# ESC2.net
KiCad netlist of a schematic drawn in EAGLE
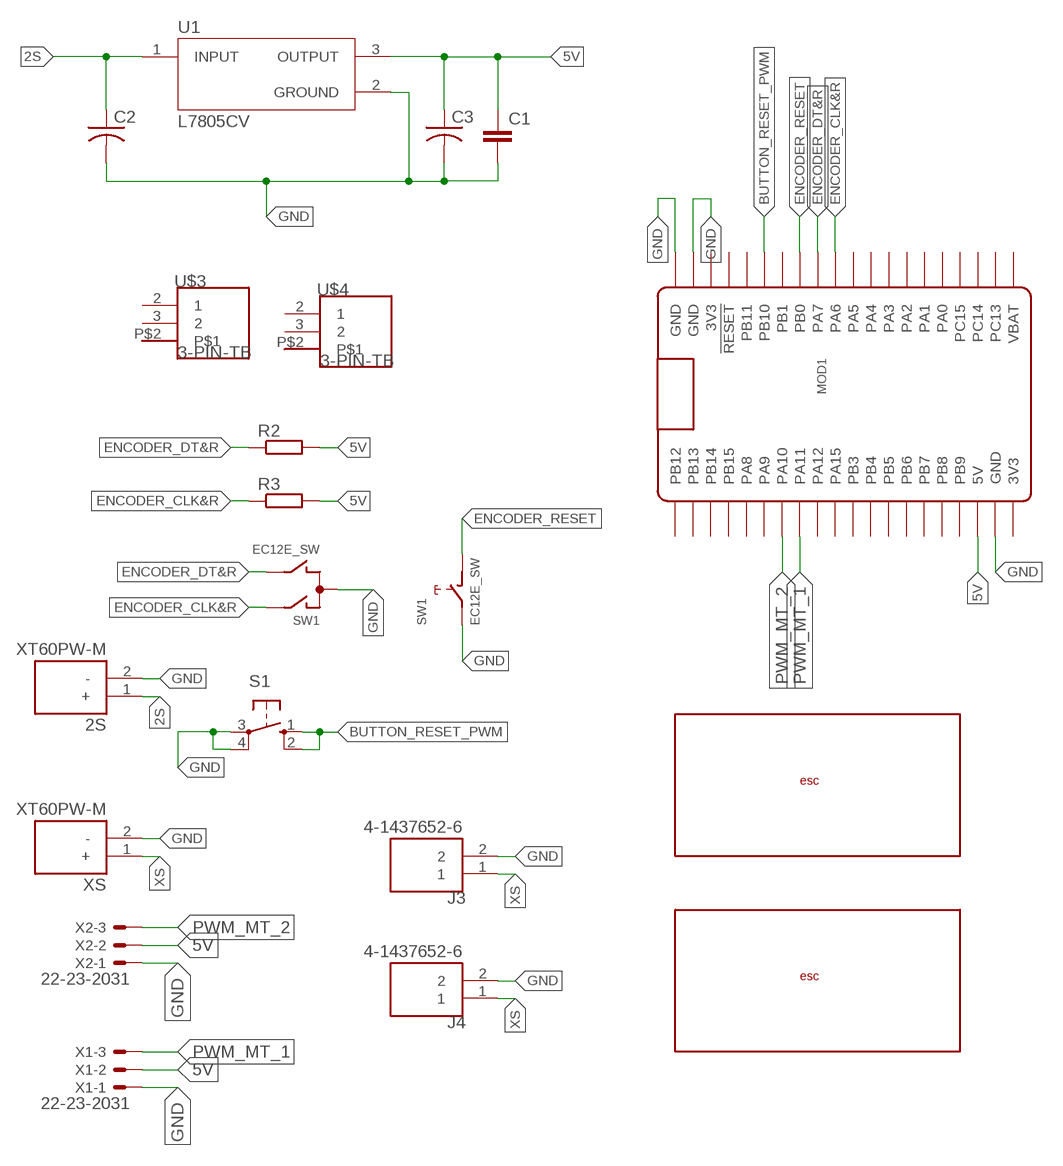
[diagram p0: schematic, sheet 1]

(export (version "E")
  (design (tool "Eeschema 10.0.6"))
  (components
    (comp (ref "2S")
      (value "XT60PW-M")
      (footprint "eagle-import:AMASS_XT60PW-M")
      (fields (field (name "MF") "AMASS"))
      (libsource (lib "eagle-import") (part "XT60PW-M"))
    )
    (comp (ref "C1")
      (value "C-EUC1206")
      (footprint "eagle-import:C1206")
      (libsource (lib "eagle-import") (part "C-EUC1206"))
    )
    (comp (ref "C2")
      (value "C-USC1206")
      (footprint "eagle-import:C1206")
      (libsource (lib "eagle-import") (part "C-USC1206"))
    )
    (comp (ref "C3")
      (value "C-USC1206")
      (footprint "eagle-import:C1206")
      (libsource (lib "eagle-import") (part "C-USC1206"))
    )
    (comp (ref "J3")
      (value "4-1437652-6")
      (footprint "eagle-import:TE_4-1437652-6")
      (fields (field (name "MF") "TE Connectivity / AMP"))
      (libsource (lib "eagle-import") (part "4-1437652-6"))
    )
    (comp (ref "J4")
      (value "4-1437652-6")
      (footprint "eagle-import:TE_4-1437652-6")
      (fields (field (name "MF") "TE Connectivity / AMP"))
      (libsource (lib "eagle-import") (part "4-1437652-6"))
    )
    (comp (ref "MOD1")
      (value "BLUE_PILL")
      (footprint "eagle-import:BLUE_PILL")
      (libsource (lib "eagle-import") (part "BLUE_PILL"))
    )
    (comp (ref "R2")
      (value "R-EU_R1206")
      (footprint "eagle-import:R1206")
      (libsource (lib "eagle-import") (part "R-EU_R1206"))
    )
    (comp (ref "R3")
      (value "R-EU_R1206")
      (footprint "eagle-import:R1206")
      (libsource (lib "eagle-import") (part "R-EU_R1206"))
    )
    (comp (ref "S1")
      (value "10-XX")
      (footprint "eagle-import:B3F-10XX")
      (fields (field (name "MPN") "B3F-1000"))
      (libsource (lib "eagle-import") (part "10-XX"))
    )
    (comp (ref "SW1")
      (value "EC12E_SW")
      (footprint "eagle-import:ALPS_EC12E_SW")
      (fields (field (name "MPN") "EC12E2424407"))
      (libsource (lib "eagle-import") (part "EC12E_SW"))
    )
    (comp (ref "U$1")
      (value "ESC_LIB")
      (footprint "eagle-import:ESC")
      (libsource (lib "eagle-import") (part "ESC_LIB"))
    )
    (comp (ref "U$2")
      (value "ESC_LIB")
      (footprint "eagle-import:ESC")
      (libsource (lib "eagle-import") (part "ESC_LIB"))
    )
    (comp (ref "U$3")
      (value "3-PIN-TB")
      (footprint "eagle-import:3-PIN-TB")
      (libsource (lib "eagle-import") (part "3-PIN-TB"))
    )
    (comp (ref "U$4")
      (value "3-PIN-TB")
      (footprint "eagle-import:3-PIN-TB")
      (libsource (lib "eagle-import") (part "3-PIN-TB"))
    )
    (comp (ref "U1")
      (value "L7805CV")
      (footprint "eagle-import:TO255P1040X460X1968-3")
      (fields (field (name "MF") "STMicroelectronics"))
      (libsource (lib "eagle-import") (part "L7805CV"))
    )
    (comp (ref "X1")
      (value "22-23-2031")
      (footprint "eagle-import:22-23-2031")
      (fields (field (name "MF") "MOLEX"))
      (libsource (lib "eagle-import") (part "22-23-2031"))
    )
    (comp (ref "X2")
      (value "22-23-2031")
      (footprint "eagle-import:22-23-2031")
      (fields (field (name "MF") "MOLEX"))
      (libsource (lib "eagle-import") (part "22-23-2031"))
    )
    (comp (ref "XS")
      (value "XT60PW-M")
      (footprint "eagle-import:AMASS_XT60PW-M")
      (fields (field (name "MF") "AMASS"))
      (libsource (lib "eagle-import") (part "XT60PW-M"))
    )
  )
  (nets
    (net (code "1") (name "2S") (class "Default")
      (node (ref "2S") (pin "1") (pinfunction "+_1") (pintype "passive"))
      (node (ref "C2") (pin "1") (pinfunction "1_1") (pintype "passive"))
      (node (ref "U1") (pin "1") (pinfunction "INPUT_1") (pintype "input"))
    )
    (net (code "2") (name "5V") (class "Default")
      (node (ref "C1") (pin "1") (pinfunction "1_1") (pintype "passive"))
      (node (ref "C3") (pin "1") (pinfunction "1_1") (pintype "passive"))
      (node (ref "MOD1") (pin "P$18") (pinfunction "5V_P$18") (pintype "bidirectional"))
      (node (ref "R2") (pin "2") (pinfunction "2_2") (pintype "passive"))
      (node (ref "R3") (pin "2") (pinfunction "2_2") (pintype "passive"))
      (node (ref "U1") (pin "3") (pinfunction "OUTPUT_3") (pintype "output"))
      (node (ref "X1") (pin "2") (pinfunction "S_2") (pintype "passive"))
      (node (ref "X2") (pin "2") (pinfunction "S_2") (pintype "passive"))
    )
    (net (code "3") (name "BUTTON_RESET_PWM") (class "Default")
      (node (ref "MOD1") (pin "P$26") (pinfunction "PB10_P$26") (pintype "bidirectional"))
      (node (ref "S1") (pin "1") (pinfunction "S_1") (pintype "passive"))
      (node (ref "S1") (pin "2") (pinfunction "S1_2") (pintype "passive"))
    )
    (net (code "4") (name "ENCODER_CLK&R") (class "Default")
      (node (ref "MOD1") (pin "P$30") (pinfunction "PA6_P$30") (pintype "bidirectional"))
      (node (ref "R3") (pin "1") (pinfunction "1_1") (pintype "passive"))
      (node (ref "SW1") (pin "A") (pinfunction "A_A") (pintype "passive"))
    )
    (net (code "5") (name "ENCODER_DT&R") (class "Default")
      (node (ref "MOD1") (pin "P$29") (pinfunction "PA7_P$29") (pintype "bidirectional"))
      (node (ref "R2") (pin "1") (pinfunction "1_1") (pintype "passive"))
      (node (ref "SW1") (pin "B") (pinfunction "B_B") (pintype "passive"))
    )
    (net (code "6") (name "ENCODER_RESET") (class "Default")
      (node (ref "MOD1") (pin "P$28") (pinfunction "PB0_P$28") (pintype "bidirectional"))
      (node (ref "SW1") (pin "D") (pinfunction "1_D") (pintype "passive"))
    )
    (net (code "7") (name "GND") (class "Default")
      (node (ref "2S") (pin "2") (pinfunction "-_2") (pintype "passive"))
      (node (ref "C1") (pin "2") (pinfunction "2_2") (pintype "passive"))
      (node (ref "C2") (pin "2") (pinfunction "2_2") (pintype "passive"))
      (node (ref "C3") (pin "2") (pinfunction "2_2") (pintype "passive"))
      (node (ref "J3") (pin "2") (pinfunction "2_2") (pintype "passive"))
      (node (ref "J4") (pin "2") (pinfunction "2_2") (pintype "passive"))
      (node (ref "MOD1") (pin "P$19") (pinfunction "GND_P$19") (pintype "passive"))
      (node (ref "MOD1") (pin "P$21") (pinfunction "GND_P$21") (pintype "passive"))
      (node (ref "MOD1") (pin "P$22") (pinfunction "GND_P$22") (pintype "passive"))
      (node (ref "S1") (pin "3") (pinfunction "P_3") (pintype "passive"))
      (node (ref "S1") (pin "4") (pinfunction "P1_4") (pintype "passive"))
      (node (ref "SW1") (pin "C") (pinfunction "C_C") (pintype "passive"))
      (node (ref "SW1") (pin "E") (pinfunction "2_E") (pintype "passive"))
      (node (ref "U1") (pin "2") (pinfunction "GROUND_2") (pintype "power_in"))
      (node (ref "X1") (pin "1") (pinfunction "S_1") (pintype "passive"))
      (node (ref "X2") (pin "1") (pinfunction "S_1") (pintype "passive"))
      (node (ref "XS") (pin "2") (pinfunction "-_2") (pintype "passive"))
    )
    (net (code "8") (name "PWM_MT_1") (class "Default")
      (node (ref "MOD1") (pin "P$8") (pinfunction "PA11_P$8") (pintype "bidirectional"))
      (node (ref "X1") (pin "3") (pinfunction "S_3") (pintype "passive"))
    )
    (net (code "9") (name "PWM_MT_2") (class "Default")
      (node (ref "MOD1") (pin "P$7") (pinfunction "PA10_P$7") (pintype "bidirectional"))
      (node (ref "X2") (pin "3") (pinfunction "S_3") (pintype "passive"))
    )
    (net (code "10") (name "XS") (class "Default")
      (node (ref "J3") (pin "1") (pinfunction "1_1") (pintype "passive"))
      (node (ref "J4") (pin "1") (pinfunction "1_1") (pintype "passive"))
      (node (ref "XS") (pin "1") (pinfunction "+_1") (pintype "passive"))
    )
    (net (code "11") (name "unconnected-(MOD1-3V3-PadP$20)") (class "Default")
      (node (ref "MOD1") (pin "P$20") (pinfunction "3V3_P$20") (pintype "bidirectional"))
    )
    (net (code "12") (name "unconnected-(MOD1-3V3-PadP$23)") (class "Default")
      (node (ref "MOD1") (pin "P$23") (pinfunction "3V3_P$23") (pintype "bidirectional"))
    )
    (net (code "13") (name "unconnected-(MOD1-PA0-PadP$36)") (class "Default")
      (node (ref "MOD1") (pin "P$36") (pinfunction "PA0_P$36") (pintype "bidirectional"))
    )
    (net (code "14") (name "unconnected-(MOD1-PA1-PadP$35)") (class "Default")
      (node (ref "MOD1") (pin "P$35") (pinfunction "PA1_P$35") (pintype "bidirectional"))
    )
    (net (code "15") (name "unconnected-(MOD1-PA2-PadP$34)") (class "Default")
      (node (ref "MOD1") (pin "P$34") (pinfunction "PA2_P$34") (pintype "bidirectional"))
    )
    (net (code "16") (name "unconnected-(MOD1-PA3-PadP$33)") (class "Default")
      (node (ref "MOD1") (pin "P$33") (pinfunction "PA3_P$33") (pintype "bidirectional"))
    )
    (net (code "17") (name "unconnected-(MOD1-PA4-PadP$32)") (class "Default")
      (node (ref "MOD1") (pin "P$32") (pinfunction "PA4_P$32") (pintype "bidirectional"))
    )
    (net (code "18") (name "unconnected-(MOD1-PA5-PadP$31)") (class "Default")
      (node (ref "MOD1") (pin "P$31") (pinfunction "PA5_P$31") (pintype "bidirectional"))
    )
    (net (code "19") (name "unconnected-(MOD1-PA8-PadP$5)") (class "Default")
      (node (ref "MOD1") (pin "P$5") (pinfunction "PA8_P$5") (pintype "bidirectional"))
    )
    (net (code "20") (name "unconnected-(MOD1-PA9-PadP$6)") (class "Default")
      (node (ref "MOD1") (pin "P$6") (pinfunction "PA9_P$6") (pintype "bidirectional"))
    )
    (net (code "21") (name "unconnected-(MOD1-PA12-PadP$9)") (class "Default")
      (node (ref "MOD1") (pin "P$9") (pinfunction "PA12_P$9") (pintype "bidirectional"))
    )
    (net (code "22") (name "unconnected-(MOD1-PA15-PadP$10)") (class "Default")
      (node (ref "MOD1") (pin "P$10") (pinfunction "PA15_P$10") (pintype "bidirectional"))
    )
    (net (code "23") (name "unconnected-(MOD1-PB1-PadP$27)") (class "Default")
      (node (ref "MOD1") (pin "P$27") (pinfunction "PB1_P$27") (pintype "bidirectional"))
    )
    (net (code "24") (name "unconnected-(MOD1-PB3-PadP$11)") (class "Default")
      (node (ref "MOD1") (pin "P$11") (pinfunction "PB3_P$11") (pintype "bidirectional"))
    )
    (net (code "25") (name "unconnected-(MOD1-PB4-PadP$12)") (class "Default")
      (node (ref "MOD1") (pin "P$12") (pinfunction "PB4_P$12") (pintype "bidirectional"))
    )
    (net (code "26") (name "unconnected-(MOD1-PB5-PadP$13)") (class "Default")
      (node (ref "MOD1") (pin "P$13") (pinfunction "PB5_P$13") (pintype "bidirectional"))
    )
    (net (code "27") (name "unconnected-(MOD1-PB6-PadP$14)") (class "Default")
      (node (ref "MOD1") (pin "P$14") (pinfunction "PB6_P$14") (pintype "bidirectional"))
    )
    (net (code "28") (name "unconnected-(MOD1-PB7-PadP$15)") (class "Default")
      (node (ref "MOD1") (pin "P$15") (pinfunction "PB7_P$15") (pintype "bidirectional"))
    )
    (net (code "29") (name "unconnected-(MOD1-PB8-PadP$16)") (class "Default")
      (node (ref "MOD1") (pin "P$16") (pinfunction "PB8_P$16") (pintype "bidirectional"))
    )
    (net (code "30") (name "unconnected-(MOD1-PB9-PadP$17)") (class "Default")
      (node (ref "MOD1") (pin "P$17") (pinfunction "PB9_P$17") (pintype "bidirectional"))
    )
    (net (code "31") (name "unconnected-(MOD1-PB11-PadP$25)") (class "Default")
      (node (ref "MOD1") (pin "P$25") (pinfunction "PB11_P$25") (pintype "bidirectional"))
    )
    (net (code "32") (name "unconnected-(MOD1-PB12-PadP$1)") (class "Default")
      (node (ref "MOD1") (pin "P$1") (pinfunction "PB12_P$1") (pintype "bidirectional"))
    )
    (net (code "33") (name "unconnected-(MOD1-PB13-PadP$2)") (class "Default")
      (node (ref "MOD1") (pin "P$2") (pinfunction "PB13_P$2") (pintype "bidirectional"))
    )
    (net (code "34") (name "unconnected-(MOD1-PB14-PadP$3)") (class "Default")
      (node (ref "MOD1") (pin "P$3") (pinfunction "PB14_P$3") (pintype "bidirectional"))
    )
    (net (code "35") (name "unconnected-(MOD1-PB15-PadP$4)") (class "Default")
      (node (ref "MOD1") (pin "P$4") (pinfunction "PB15_P$4") (pintype "bidirectional"))
    )
    (net (code "36") (name "unconnected-(MOD1-PC13-PadP$39)") (class "Default")
      (node (ref "MOD1") (pin "P$39") (pinfunction "PC13_P$39") (pintype "bidirectional"))
    )
    (net (code "37") (name "unconnected-(MOD1-PC14-PadP$38)") (class "Default")
      (node (ref "MOD1") (pin "P$38") (pinfunction "PC14_P$38") (pintype "bidirectional"))
    )
    (net (code "38") (name "unconnected-(MOD1-PC15-PadP$37)") (class "Default")
      (node (ref "MOD1") (pin "P$37") (pinfunction "PC15_P$37") (pintype "bidirectional"))
    )
    (net (code "39") (name "unconnected-(MOD1-VBAT-PadP$40)") (class "Default")
      (node (ref "MOD1") (pin "P$40") (pinfunction "VBAT_P$40") (pintype "bidirectional"))
    )
    (net (code "40") (name "unconnected-(MOD1-~{RESET}-PadP$24)") (class "Default")
      (node (ref "MOD1") (pin "P$24") (pinfunction "~{RESET}_P$24") (pintype "bidirectional"))
    )
    (net (code "41") (name "unconnected-(U$3-1-Pad2)") (class "Default")
      (node (ref "U$3") (pin "2") (pinfunction "1_2") (pintype "passive"))
    )
    (net (code "42") (name "unconnected-(U$3-2-Pad3)") (class "Default")
      (node (ref "U$3") (pin "3") (pinfunction "2_3") (pintype "passive"))
    )
    (net (code "43") (name "unconnected-(U$3-P$1-PadP$2)") (class "Default")
      (node (ref "U$3") (pin "P$2") (pinfunction "P$1_P$2") (pintype "bidirectional"))
    )
    (net (code "44") (name "unconnected-(U$4-1-Pad2)") (class "Default")
      (node (ref "U$4") (pin "2") (pinfunction "1_2") (pintype "passive"))
    )
    (net (code "45") (name "unconnected-(U$4-2-Pad3)") (class "Default")
      (node (ref "U$4") (pin "3") (pinfunction "2_3") (pintype "passive"))
    )
    (net (code "46") (name "unconnected-(U$4-P$1-PadP$2)") (class "Default")
      (node (ref "U$4") (pin "P$2") (pinfunction "P$1_P$2") (pintype "bidirectional"))
    )
  )
)
